# RelayDriver.net
KiCad netlist of a schematic drawn in Altium Designer
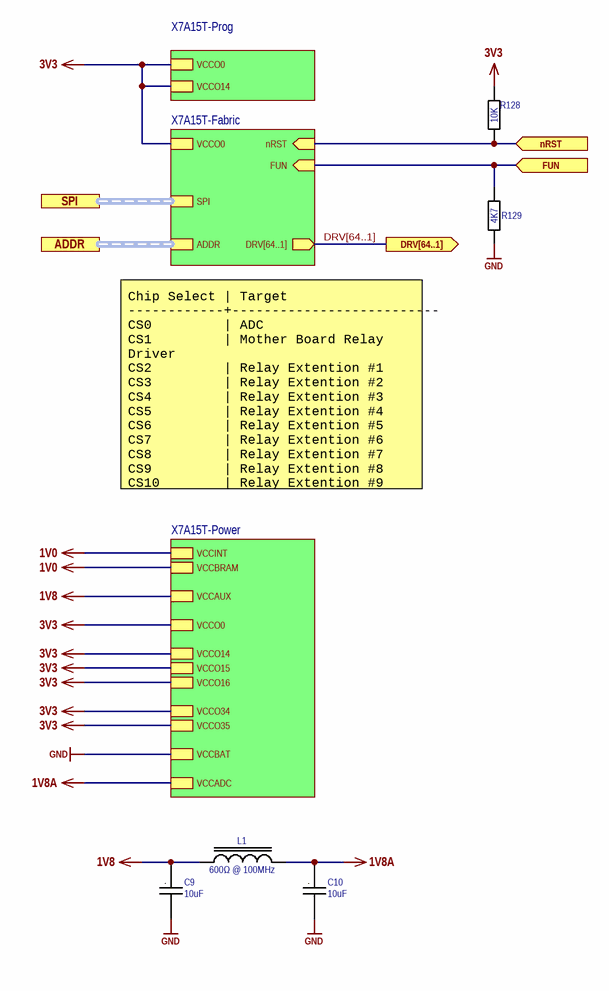
[diagram p0: RelayDriver.SchDoc]

(export (version "E")
  (design (tool "Eeschema 10.0.6"))
  (components
    (comp (ref "C9")
      (value "10uF")
      (footprint "C0805 Reflow")
      (description "CAP CER 10UF 10V X7R 0805")
      (fields
        (field (name "TOLERANCE") "±10%")
        (field (name "02. DISTRIBUTOR PART NUMBER") "1276-1764-6-ND")
        (field (name "13. CREATED DATE/NAME") "AUG2018/Hören")
      )
      (libsource (lib "chickenfood") (part "C"))
    )
    (comp (ref "C10")
      (value "10uF")
      (footprint "C0805 Reflow")
      (description "CAP CER 10UF 10V X7R 0805")
      (fields
        (field (name "TOLERANCE") "±10%")
        (field (name "02. DISTRIBUTOR PART NUMBER") "1276-1764-6-ND")
        (field (name "13. CREATED DATE/NAME") "AUG2018/Hören")
      )
      (libsource (lib "chickenfood") (part "C"))
    )
    (comp (ref "L1")
      (value "L")
      (footprint "FB0805")
      (description "FERRITE BEAD 600 OHM 0805 1LN")
      (fields
        (field (name "NOMINAL IMPEDANCE") "600Ω @ 100MHz")
        (field (name "02. DISTRIBUTOR PART NUMBER") "732-1620-6-ND")
        (field (name "07. MANUFACTURER  PART NUMBER") "742792040")
        (field (name "13. CREATED DATE/NAME") "AUG2018/Hören")
      )
      (libsource (lib "chickenfood") (part "FB"))
    )
    (comp (ref "R128")
      (value "10K")
      (footprint "R0402 Reflow")
      (description "RES SMD 10K OHM 1% 1/16W 0402")
      (fields
        (field (name "TOLERANCE") "±1%")
        (field (name "02. DISTRIBUTOR PART NUMBER") "311-10.0KLRDKR-ND")
        (field (name "13. CREATED DATE/NAME") "AUG2018/Hören")
      )
      (libsource (lib "chickenfood") (part "R"))
    )
    (comp (ref "R129")
      (value "4K7")
      (footprint "R0402 Reflow")
      (description "RES SMD 4.7K OHM 1% 1/16W 0402")
      (fields
        (field (name "TOLERANCE") "±1%")
        (field (name "02. DISTRIBUTOR PART NUMBER") "311-4.7KLRDKR-ND")
        (field (name "13. CREATED DATE/NAME") "AUG2018/Hören")
      )
      (libsource (lib "") (part "R_1"))
    )
  )
  (nets
    (net (code "69") (name "/FUN") (class "Default")
      (node (ref "R129") (pin "2") (pinfunction "2_2") (pintype "passive"))
    )
    (net (code "71") (name "/nRST") (class "Default")
      (node (ref "R128") (pin "2") (pinfunction "2_2") (pintype "passive"))
    )
    (net (code "73") (name "1V8") (class "Default")
      (node (ref "C9") (pin "1") (pinfunction "1_1") (pintype "passive"))
      (node (ref "L1") (pin "1") (pinfunction "1_1") (pintype "passive"))
    )
    (net (code "74") (name "1V8A") (class "Default")
      (node (ref "C10") (pin "1") (pinfunction "1_1") (pintype "passive"))
      (node (ref "L1") (pin "2") (pinfunction "2_2") (pintype "passive"))
    )
    (net (code "75") (name "3V3") (class "Default")
      (node (ref "R128") (pin "1") (pinfunction "1_1") (pintype "passive"))
    )
    (net (code "76") (name "GND") (class "Default")
      (node (ref "C10") (pin "2") (pinfunction "2_2") (pintype "passive"))
      (node (ref "C9") (pin "2") (pinfunction "2_2") (pintype "passive"))
      (node (ref "R129") (pin "1") (pinfunction "1_1") (pintype "passive"))
    )
  )
)
